# MSP430.net
KiCad netlist of a schematic drawn in Altium Designer
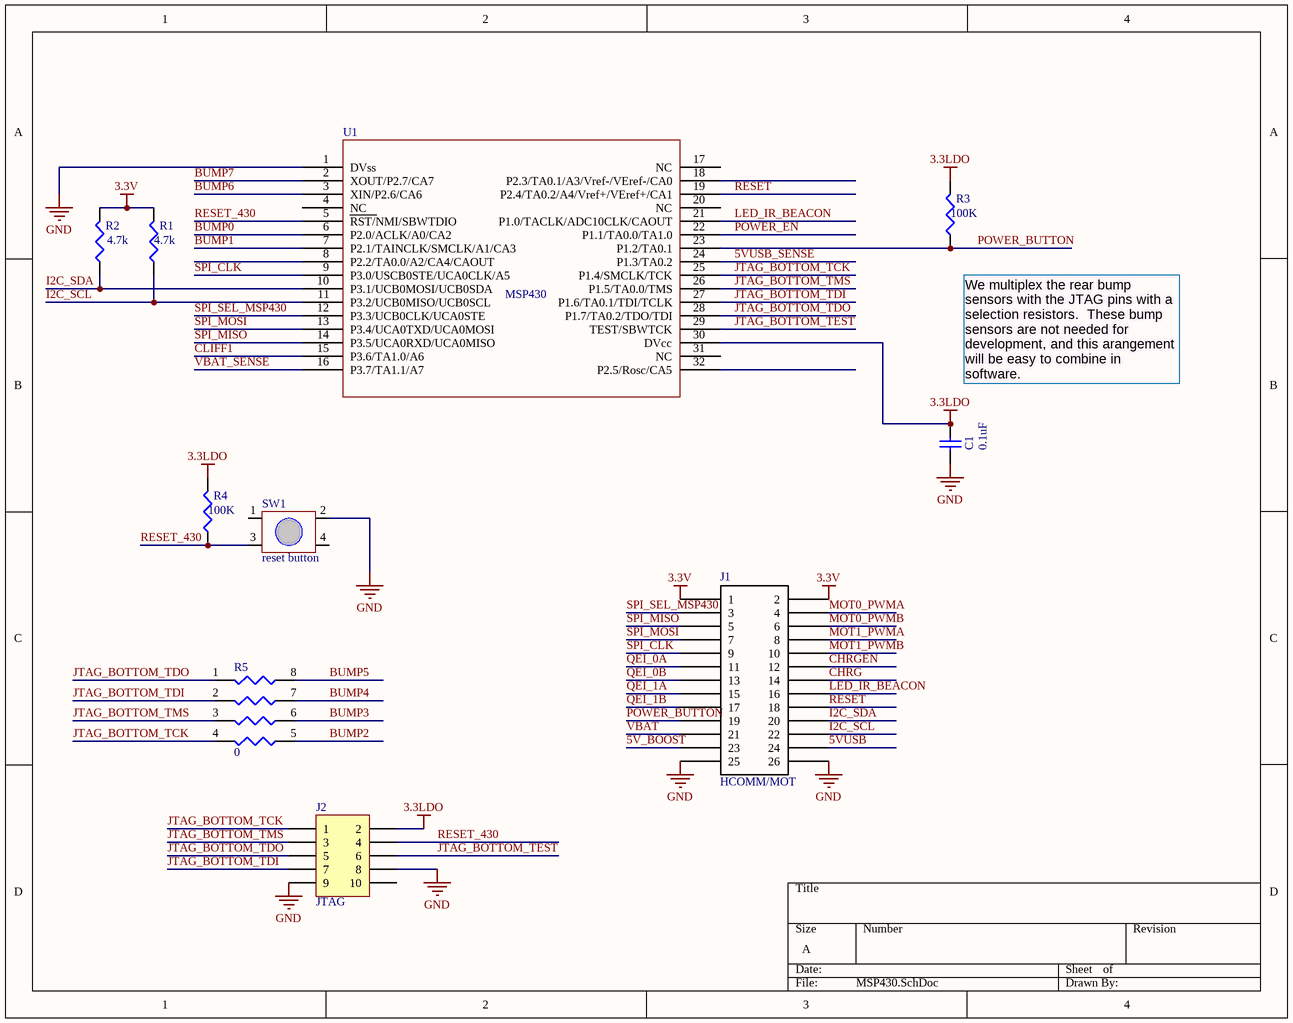
[diagram p0: MSP430.SchDoc]

(export (version "E")
  (design (tool "Eeschema 10.0.6"))
  (components
    (comp (ref "C1")
      (value "0.1uF")
      (footprint "CAPC1005L")
      (description "Capacitor (Semiconductor SIM Model)")
      (fields (field (name "Comment") "Cap Semi") (field (name "PUBLISHER") "Altium Limited"))
      (libsource (lib "Miscellaneous Devices") (part "Cap Semi"))
    )
    (comp (ref "J1")
      (value "HCOMM/MOT")
      (footprint "HeaderSM 13x2")
      (description "Header, 2X20, 50mil, IDC")
      (libsource (lib "mrone") (part "HCOMM/HMOT"))
    )
    (comp (ref "J2")
      (value "JTAG")
      (footprint "HDR2X5")
      (description "Header, 5-Pin, Dual row")
      (fields (field (name "PUBLISHER") "Altium Limited"))
      (libsource (lib "Miscellaneous Connectors") (part "Header 5X2"))
    )
    (comp (ref "R1")
      (value "4.7k")
      (footprint "RESC1608L")
      (description "Resistor")
      (fields (field (name "Comment") "Res3") (field (name "PUBLISHER") "Altium Limited"))
      (libsource (lib "Miscellaneous Devices") (part "Res3"))
    )
    (comp (ref "R2")
      (value "4.7k")
      (footprint "RESC1608L")
      (description "Resistor")
      (fields (field (name "Comment") "Res3") (field (name "PUBLISHER") "Altium Limited"))
      (libsource (lib "Miscellaneous Devices") (part "Res3"))
    )
    (comp (ref "R3")
      (value "100K")
      (footprint "RESC1608L")
      (description "Resistor")
      (fields (field (name "Comment") "Res3") (field (name "PUBLISHER") "Altium Limited"))
      (libsource (lib "Miscellaneous Devices") (part "Res3"))
    )
    (comp (ref "R4")
      (value "100K")
      (footprint "RESC1608L")
      (description "Resistor")
      (fields (field (name "Comment") "Res3") (field (name "PUBLISHER") "Altium Limited"))
      (libsource (lib "Miscellaneous Devices") (part "Res3"))
    )
    (comp (ref "R5") (value "0") (footprint "4-RES ARRAY") (libsource (lib "mrone") (part "4 Res Array")))
    (comp (ref "SW1")
      (value "reset button")
      (footprint "SwitchTall-TL330")
      (libsource (lib "mrone") (part "Switch-TL330"))
    )
    (comp (ref "U1")
      (value "MSP430")
      (footprint "MSP430_32PIN")
      (libsource (lib "mrone") (part "MSP430_32pin"))
    )
  )
  (nets
    (net (code "1") (name "/5VUSB") (class "Default")
      (node (ref "J1") (pin "24") (pinfunction "24_24") (pintype "passive"))
    )
    (net (code "2") (name "/5VUSB_SENSE") (class "Default")
      (node (ref "U1") (pin "24") (pinfunction "P1.3/TA0.2_24") (pintype "passive"))
    )
    (net (code "3") (name "/5V_BOOST") (class "Default")
      (node (ref "J1") (pin "23") (pinfunction "23_23") (pintype "passive"))
    )
    (net (code "4") (name "/BUMP0") (class "Default")
      (node (ref "U1") (pin "6") (pinfunction "P2.0/ACLK/A0/CA2_6") (pintype "passive"))
    )
    (net (code "5") (name "/BUMP1") (class "Default")
      (node (ref "U1") (pin "7") (pinfunction "P2.1/TAINCLK/SMCLK/A1/CA3_7") (pintype "passive"))
    )
    (net (code "6") (name "/BUMP2") (class "Default")
      (node (ref "R5") (pin "5") (pinfunction "5_5") (pintype "passive"))
    )
    (net (code "7") (name "/BUMP3") (class "Default")
      (node (ref "R5") (pin "6") (pinfunction "6_6") (pintype "passive"))
    )
    (net (code "8") (name "/BUMP4") (class "Default")
      (node (ref "R5") (pin "7") (pinfunction "7_7") (pintype "passive"))
    )
    (net (code "9") (name "/BUMP5") (class "Default")
      (node (ref "R5") (pin "8") (pinfunction "8_8") (pintype "passive"))
    )
    (net (code "10") (name "/BUMP6") (class "Default")
      (node (ref "U1") (pin "3") (pinfunction "XIN/P2.6/CA6_3") (pintype "passive"))
    )
    (net (code "11") (name "/BUMP7") (class "Default")
      (node (ref "U1") (pin "2") (pinfunction "XOUT/P2.7/CA7_2") (pintype "passive"))
    )
    (net (code "12") (name "/CHRG") (class "Default")
      (node (ref "J1") (pin "14") (pinfunction "14_14") (pintype "passive"))
    )
    (net (code "13") (name "/CHRGEN") (class "Default")
      (node (ref "J1") (pin "12") (pinfunction "12_12") (pintype "passive"))
    )
    (net (code "14") (name "/CLIFF1") (class "Default")
      (node (ref "U1") (pin "15") (pinfunction "P3.6/TA1.0/A6_15") (pintype "passive"))
    )
    (net (code "15") (name "/I2C_SCL") (class "Default")
      (node (ref "J1") (pin "22") (pinfunction "22_22") (pintype "passive"))
      (node (ref "R1") (pin "1") (pinfunction "1_1") (pintype "passive"))
      (node (ref "U1") (pin "11") (pinfunction "P3.2/UCB0MISO/UCB0SCL_11") (pintype "passive"))
    )
    (net (code "16") (name "/I2C_SDA") (class "Default")
      (node (ref "J1") (pin "20") (pinfunction "20_20") (pintype "passive"))
      (node (ref "R2") (pin "1") (pinfunction "1_1") (pintype "passive"))
      (node (ref "U1") (pin "10") (pinfunction "P3.1/UCB0MOSI/UCB0SDA_10") (pintype "passive"))
    )
    (net (code "17") (name "/JTAG_BOTTOM_TCK") (class "Default")
      (node (ref "J2") (pin "1") (pinfunction "1_1") (pintype "passive"))
      (node (ref "R5") (pin "4") (pinfunction "4_4") (pintype "passive"))
      (node (ref "U1") (pin "25") (pinfunction "P1.4/SMCLK/TCK_25") (pintype "passive"))
    )
    (net (code "18") (name "/JTAG_BOTTOM_TDI") (class "Default")
      (node (ref "J2") (pin "7") (pinfunction "7_7") (pintype "passive"))
      (node (ref "R5") (pin "2") (pinfunction "2_2") (pintype "passive"))
      (node (ref "U1") (pin "27") (pinfunction "P1.6/TA0.1/TDI/TCLK_27") (pintype "passive"))
    )
    (net (code "19") (name "/JTAG_BOTTOM_TDO") (class "Default")
      (node (ref "J2") (pin "5") (pinfunction "5_5") (pintype "passive"))
      (node (ref "R5") (pin "1") (pinfunction "1_1") (pintype "passive"))
      (node (ref "U1") (pin "28") (pinfunction "P1.7/TA0.2/TDO/TDI_28") (pintype "passive"))
    )
    (net (code "20") (name "/JTAG_BOTTOM_TEST") (class "Default")
      (node (ref "J2") (pin "6") (pinfunction "6_6") (pintype "passive"))
      (node (ref "U1") (pin "29") (pinfunction "TEST/SBWTCK_29") (pintype "passive"))
    )
    (net (code "21") (name "/JTAG_BOTTOM_TMS") (class "Default")
      (node (ref "J2") (pin "3") (pinfunction "3_3") (pintype "passive"))
      (node (ref "R5") (pin "3") (pinfunction "3_3") (pintype "passive"))
      (node (ref "U1") (pin "26") (pinfunction "P1.5/TA0.0/TMS_26") (pintype "passive"))
    )
    (net (code "22") (name "/LED_IR_BEACON") (class "Default")
      (node (ref "J1") (pin "16") (pinfunction "16_16") (pintype "passive"))
      (node (ref "U1") (pin "21") (pinfunction "P1.0/TACLK/ADC10CLK/CAOUT_21") (pintype "passive"))
    )
    (net (code "23") (name "/MOT0_PWMA") (class "Default")
      (node (ref "J1") (pin "4") (pinfunction "4_4") (pintype "passive"))
    )
    (net (code "24") (name "/MOT0_PWMB") (class "Default")
      (node (ref "J1") (pin "6") (pinfunction "6_6") (pintype "passive"))
    )
    (net (code "25") (name "/MOT1_PWMA") (class "Default")
      (node (ref "J1") (pin "8") (pinfunction "8_8") (pintype "passive"))
    )
    (net (code "26") (name "/MOT1_PWMB") (class "Default")
      (node (ref "J1") (pin "10") (pinfunction "10_10") (pintype "passive"))
    )
    (net (code "27") (name "/POWER_BUTTON") (class "Default")
      (node (ref "J1") (pin "19") (pinfunction "19_19") (pintype "passive"))
      (node (ref "R3") (pin "1") (pinfunction "1_1") (pintype "passive"))
      (node (ref "U1") (pin "23") (pinfunction "P1.2/TA0.1_23") (pintype "passive"))
    )
    (net (code "28") (name "/POWER_EN") (class "Default")
      (node (ref "U1") (pin "22") (pinfunction "P1.1/TA0.0/TA1.0_22") (pintype "passive"))
    )
    (net (code "29") (name "/QEI_0A") (class "Default")
      (node (ref "J1") (pin "11") (pinfunction "11_11") (pintype "passive"))
    )
    (net (code "30") (name "/QEI_0B") (class "Default")
      (node (ref "J1") (pin "13") (pinfunction "13_13") (pintype "passive"))
    )
    (net (code "31") (name "/QEI_1A") (class "Default")
      (node (ref "J1") (pin "15") (pinfunction "15_15") (pintype "passive"))
    )
    (net (code "32") (name "/QEI_1B") (class "Default")
      (node (ref "J1") (pin "17") (pinfunction "17_17") (pintype "passive"))
    )
    (net (code "33") (name "/RESET") (class "Default")
      (node (ref "J1") (pin "18") (pinfunction "18_18") (pintype "passive"))
      (node (ref "U1") (pin "19") (pinfunction "P2.4/TA0.2/A4/Vref+/VEref+/CA1_19") (pintype "passive"))
    )
    (net (code "34") (name "/RESET_430") (class "Default")
      (node (ref "J2") (pin "4") (pinfunction "4_4") (pintype "passive"))
      (node (ref "R4") (pin "1") (pinfunction "1_1") (pintype "passive"))
      (node (ref "SW1") (pin "3") (pinfunction "3_3") (pintype "passive"))
      (node (ref "U1") (pin "5") (pinfunction "RST/NMI/SBWTDIO_5") (pintype "passive"))
    )
    (net (code "35") (name "/SPI_CLK") (class "Default")
      (node (ref "J1") (pin "9") (pinfunction "9_9") (pintype "passive"))
      (node (ref "U1") (pin "9") (pinfunction "P3.0/USCB0STE/UCA0CLK/A5_9") (pintype "passive"))
    )
    (net (code "36") (name "/SPI_MISO") (class "Default")
      (node (ref "J1") (pin "5") (pinfunction "5_5") (pintype "passive"))
      (node (ref "U1") (pin "14") (pinfunction "P3.5/UCA0RXD/UCA0MISO_14") (pintype "passive"))
    )
    (net (code "37") (name "/SPI_MOSI") (class "Default")
      (node (ref "J1") (pin "7") (pinfunction "7_7") (pintype "passive"))
      (node (ref "U1") (pin "13") (pinfunction "P3.4/UCA0TXD/UCA0MOSI_13") (pintype "passive"))
    )
    (net (code "38") (name "/SPI_SEL_MSP430") (class "Default")
      (node (ref "J1") (pin "3") (pinfunction "3_3") (pintype "passive"))
      (node (ref "U1") (pin "12") (pinfunction "P3.3/UCB0CLK/UCA0STE_12") (pintype "passive"))
    )
    (net (code "39") (name "/VBAT") (class "Default")
      (node (ref "J1") (pin "21") (pinfunction "21_21") (pintype "passive"))
    )
    (net (code "40") (name "/VBAT_SENSE") (class "Default")
      (node (ref "U1") (pin "16") (pinfunction "P3.7/TA1.1/A7_16") (pintype "passive"))
    )
    (net (code "41") (name "3.3LDO") (class "Default")
      (node (ref "C1") (pin "2") (pinfunction "2_2") (pintype "passive"))
      (node (ref "J2") (pin "2") (pinfunction "2_2") (pintype "passive"))
      (node (ref "R3") (pin "2") (pinfunction "2_2") (pintype "passive"))
      (node (ref "R4") (pin "2") (pinfunction "2_2") (pintype "passive"))
      (node (ref "U1") (pin "30") (pinfunction "DVcc_30") (pintype "passive"))
    )
    (net (code "42") (name "3.3V") (class "Default")
      (node (ref "J1") (pin "1") (pinfunction "1_1") (pintype "passive"))
      (node (ref "J1") (pin "2") (pinfunction "2_2") (pintype "passive"))
      (node (ref "R1") (pin "2") (pinfunction "2_2") (pintype "passive"))
      (node (ref "R2") (pin "2") (pinfunction "2_2") (pintype "passive"))
    )
    (net (code "43") (name "GND") (class "Default")
      (node (ref "C1") (pin "1") (pinfunction "1_1") (pintype "passive"))
      (node (ref "J1") (pin "25") (pinfunction "25_25") (pintype "passive"))
      (node (ref "J1") (pin "26") (pinfunction "26_26") (pintype "passive"))
      (node (ref "J2") (pin "8") (pinfunction "8_8") (pintype "passive"))
      (node (ref "J2") (pin "9") (pinfunction "9_9") (pintype "passive"))
      (node (ref "SW1") (pin "2") (pinfunction "2_2") (pintype "passive"))
      (node (ref "U1") (pin "1") (pinfunction "DVss_1") (pintype "passive"))
    )
    (net (code "44") (name "unconnected-(J2-Pad10)") (class "Default")
      (node (ref "J2") (pin "10") (pinfunction "10_10") (pintype "passive"))
    )
    (net (code "45") (name "unconnected-(R5-Pad1)") (class "Default")
      (node (ref "R5") (pin "1") (pinfunction "1_1") (pintype "passive"))
    )
    (net (code "46") (name "unconnected-(R5-Pad1)_1") (class "Default")
      (node (ref "R5") (pin "1") (pinfunction "1_1") (pintype "passive"))
    )
    (net (code "47") (name "unconnected-(R5-Pad1)_2") (class "Default")
      (node (ref "R5") (pin "1") (pinfunction "1_1") (pintype "passive"))
    )
    (net (code "48") (name "unconnected-(R5-Pad1)_3") (class "Default")
      (node (ref "R5") (pin "1") (pinfunction "1_1") (pintype "passive"))
    )
    (net (code "49") (name "unconnected-(R5-Pad2)") (class "Default")
      (node (ref "R5") (pin "2") (pinfunction "2_2") (pintype "passive"))
    )
    (net (code "50") (name "unconnected-(R5-Pad2)_1") (class "Default")
      (node (ref "R5") (pin "2") (pinfunction "2_2") (pintype "passive"))
    )
    (net (code "51") (name "unconnected-(R5-Pad2)_2") (class "Default")
      (node (ref "R5") (pin "2") (pinfunction "2_2") (pintype "passive"))
    )
    (net (code "52") (name "unconnected-(R5-Pad2)_3") (class "Default")
      (node (ref "R5") (pin "2") (pinfunction "2_2") (pintype "passive"))
    )
    (net (code "53") (name "unconnected-(SW1-Pad1)") (class "Default")
      (node (ref "SW1") (pin "1") (pinfunction "1_1") (pintype "passive"))
    )
    (net (code "54") (name "unconnected-(SW1-Pad4)") (class "Default")
      (node (ref "SW1") (pin "4") (pinfunction "4_4") (pintype "passive"))
    )
    (net (code "55") (name "unconnected-(U1-NC-Pad4)") (class "Default")
      (node (ref "U1") (pin "4") (pinfunction "NC_4") (pintype "passive"))
    )
    (net (code "56") (name "unconnected-(U1-NC-Pad17)") (class "Default")
      (node (ref "U1") (pin "17") (pinfunction "NC_17") (pintype "passive"))
    )
    (net (code "57") (name "unconnected-(U1-NC-Pad20)") (class "Default")
      (node (ref "U1") (pin "20") (pinfunction "NC_20") (pintype "passive"))
    )
    (net (code "58") (name "unconnected-(U1-NC-Pad31)") (class "Default")
      (node (ref "U1") (pin "31") (pinfunction "NC_31") (pintype "passive"))
    )
    (net (code "59") (name "unconnected-(U1-P2.2{slash}TA0.0{slash}A2{slash}CA4{slash}CAOUT-Pad8)") (class "Default")
      (node (ref "U1") (pin "8") (pinfunction "P2.2/TA0.0/A2/CA4/CAOUT_8") (pintype "passive"))
    )
    (net (code "60") (name "unconnected-(U1-P2.3{slash}TA0.1{slash}A3{slash}Vref-{slash}VEref-{slash}CA0-Pad18)") (class "Default")
      (node (ref "U1") (pin "18") (pinfunction "P2.3/TA0.1/A3/Vref-/VEref-/CA0_18") (pintype "passive"))
    )
    (net (code "61") (name "unconnected-(U1-P2.5{slash}Rosc{slash}CA5-Pad32)") (class "Default")
      (node (ref "U1") (pin "32") (pinfunction "P2.5/Rosc/CA5_32") (pintype "passive"))
    )
  )
)
